# Sheet_Switch_PowerDetect.net
KiCad netlist of a schematic drawn in Altium Designer
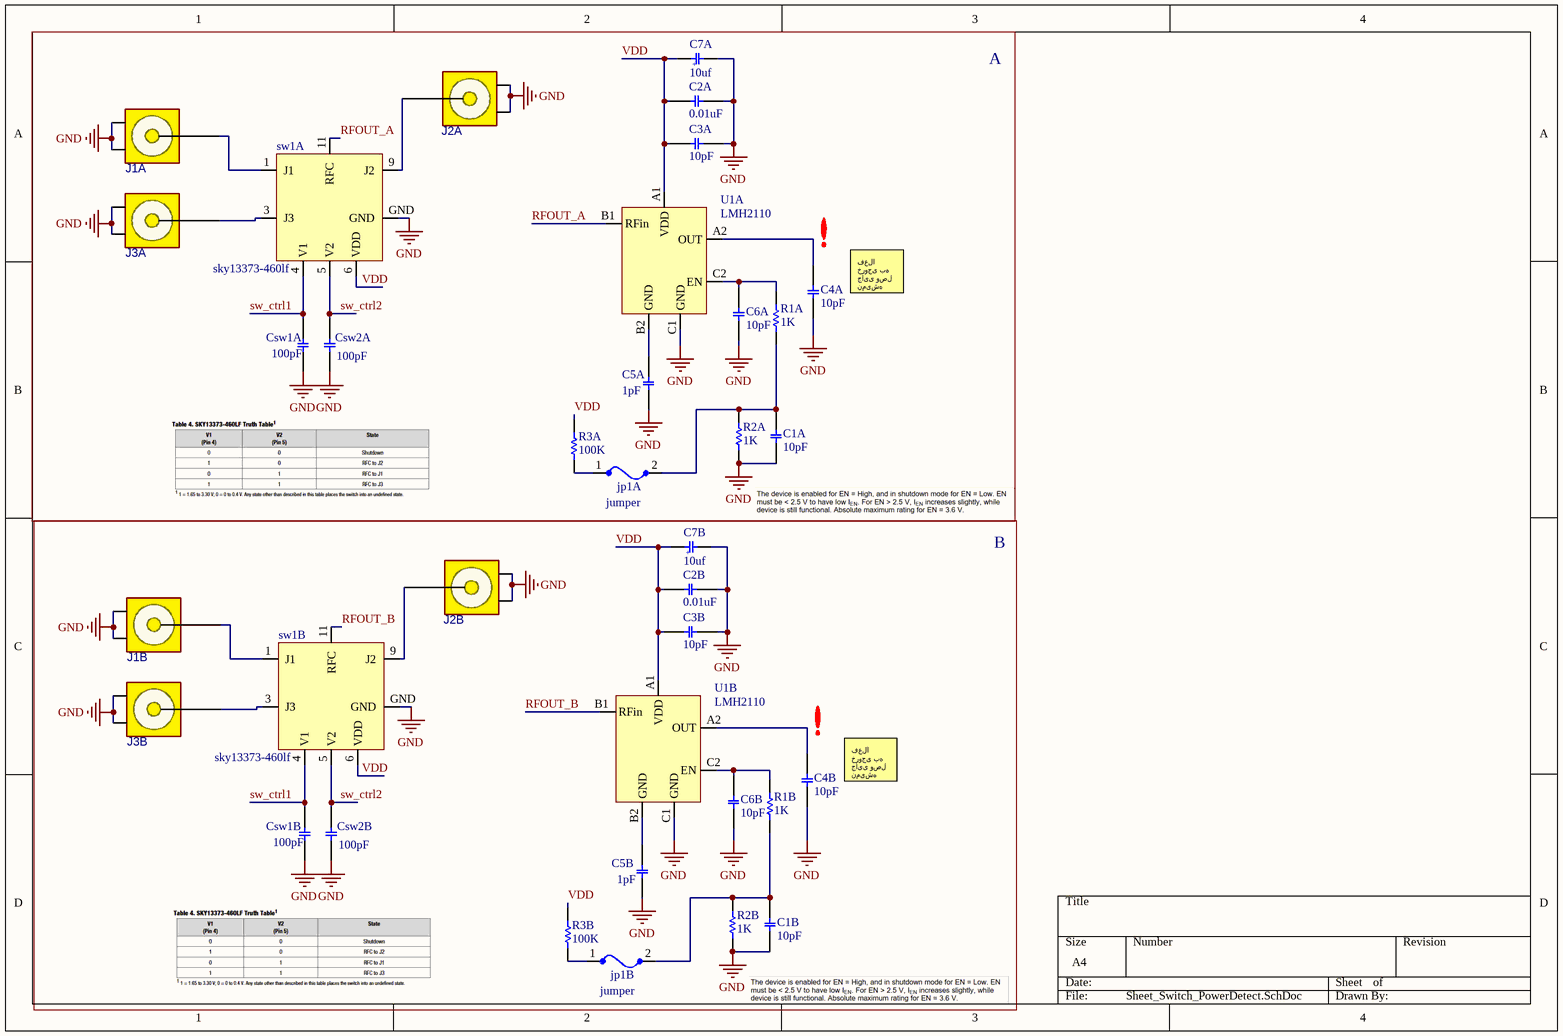
[diagram p0: Sheet_Switch_PowerDetect.SchDoc]

(export (version "E")
  (design (tool "Eeschema 10.0.6"))
  (components
    (comp (ref "C1A")
      (value "10pF")
      (footprint "C0402")
      (description "Capacitor C SMD 0402")
      (fields (field (name "DESIGNED BY:") "MJKhodami"))
      (libsource (lib "project_library") (part "Capacitor C SMD 0402"))
    )
    (comp (ref "C1B")
      (value "10pF")
      (footprint "C0402")
      (description "Capacitor C SMD 0402")
      (fields (field (name "DESIGNED BY:") "MJKhodami"))
      (libsource (lib "project_library") (part "Capacitor C SMD 0402"))
    )
    (comp (ref "C2A")
      (value "0.01uF")
      (footprint "C0402")
      (description "Capacitor C SMD 0402")
      (fields (field (name "DESIGNED BY:") "MJKhodami"))
      (libsource (lib "project_library") (part "Capacitor C SMD 0402"))
    )
    (comp (ref "C2B")
      (value "0.01uF")
      (footprint "C0402")
      (description "Capacitor C SMD 0402")
      (fields (field (name "DESIGNED BY:") "MJKhodami"))
      (libsource (lib "project_library") (part "Capacitor C SMD 0402"))
    )
    (comp (ref "C3A")
      (value "10pF")
      (footprint "C0402")
      (description "Capacitor C SMD 0402")
      (fields (field (name "DESIGNED BY:") "MJKhodami"))
      (libsource (lib "project_library") (part "Capacitor C SMD 0402"))
    )
    (comp (ref "C3B")
      (value "10pF")
      (footprint "C0402")
      (description "Capacitor C SMD 0402")
      (fields (field (name "DESIGNED BY:") "MJKhodami"))
      (libsource (lib "project_library") (part "Capacitor C SMD 0402"))
    )
    (comp (ref "C4A")
      (value "10pF")
      (footprint "C0402")
      (description "Capacitor C SMD 0402")
      (fields (field (name "DESIGNED BY:") "MJKhodami"))
      (libsource (lib "project_library") (part "Capacitor C SMD 0402"))
    )
    (comp (ref "C4B")
      (value "10pF")
      (footprint "C0402")
      (description "Capacitor C SMD 0402")
      (fields (field (name "DESIGNED BY:") "MJKhodami"))
      (libsource (lib "project_library") (part "Capacitor C SMD 0402"))
    )
    (comp (ref "C5A")
      (value "1pF")
      (footprint "C0402")
      (description "Capacitor C SMD 0402")
      (fields (field (name "DESIGNED BY:") "MJKhodami"))
      (libsource (lib "project_library") (part "Capacitor C SMD 0402"))
    )
    (comp (ref "C5B")
      (value "1pF")
      (footprint "C0402")
      (description "Capacitor C SMD 0402")
      (fields (field (name "DESIGNED BY:") "MJKhodami"))
      (libsource (lib "project_library") (part "Capacitor C SMD 0402"))
    )
    (comp (ref "C6A")
      (value "10pF")
      (footprint "C0402")
      (description "Capacitor C SMD 0402")
      (fields (field (name "DESIGNED BY:") "MJKhodami"))
      (libsource (lib "project_library") (part "Capacitor C SMD 0402"))
    )
    (comp (ref "C6B")
      (value "10pF")
      (footprint "C0402")
      (description "Capacitor C SMD 0402")
      (fields (field (name "DESIGNED BY:") "MJKhodami"))
      (libsource (lib "project_library") (part "Capacitor C SMD 0402"))
    )
    (comp (ref "C7A")
      (value "10uf")
      (footprint "CAPP 1206 (3216X18L) Size A")
      (description "Capacitor Tantalum SMD")
      (fields (field (name "DESIGNED BY:") "MJKhodami"))
      (libsource (lib "project_library") (part "Capacitor Tantalum SMD"))
    )
    (comp (ref "C7B")
      (value "10uf")
      (footprint "CAPP 1206 (3216X18L) Size A")
      (description "Capacitor Tantalum SMD")
      (fields (field (name "DESIGNED BY:") "MJKhodami"))
      (libsource (lib "project_library") (part "Capacitor Tantalum SMD"))
    )
    (comp (ref "Csw1A")
      (value "100pF")
      (footprint "C0402")
      (description "Capacitor C SMD 0402")
      (fields (field (name "DESIGNED BY:") "MJKhodami"))
      (libsource (lib "project_library") (part "Capacitor C SMD 0402"))
    )
    (comp (ref "Csw1B")
      (value "100pF")
      (footprint "C0402")
      (description "Capacitor C SMD 0402")
      (fields (field (name "DESIGNED BY:") "MJKhodami"))
      (libsource (lib "project_library") (part "Capacitor C SMD 0402"))
    )
    (comp (ref "Csw2A")
      (value "100pF")
      (footprint "C0402")
      (description "Capacitor C SMD 0402")
      (fields (field (name "DESIGNED BY:") "MJKhodami"))
      (libsource (lib "project_library") (part "Capacitor C SMD 0402"))
    )
    (comp (ref "Csw2B")
      (value "100pF")
      (footprint "C0402")
      (description "Capacitor C SMD 0402")
      (fields (field (name "DESIGNED BY:") "MJKhodami"))
      (libsource (lib "project_library") (part "Capacitor C SMD 0402"))
    )
    (comp (ref "J1A")
      (value "UFL")
      (footprint "UFL")
      (description "CONN, RF, U.FL, STRAIGHT, Ultra Miniature Coaxial")
      (fields (field (name "DESIGNED BY:") "MJKhodami"))
      (libsource (lib "project_library") (part "RF UFL"))
    )
    (comp (ref "J1B")
      (value "UFL")
      (footprint "UFL")
      (description "CONN, RF, U.FL, STRAIGHT, Ultra Miniature Coaxial")
      (fields (field (name "DESIGNED BY:") "MJKhodami"))
      (libsource (lib "project_library") (part "RF UFL"))
    )
    (comp (ref "J2A")
      (value "UFL")
      (footprint "UFL")
      (description "CONN, RF, U.FL, STRAIGHT, Ultra Miniature Coaxial")
      (fields (field (name "DESIGNED BY:") "MJKhodami"))
      (libsource (lib "") (part "RF UFL_1"))
    )
    (comp (ref "J2B")
      (value "UFL")
      (footprint "UFL")
      (description "CONN, RF, U.FL, STRAIGHT, Ultra Miniature Coaxial")
      (fields (field (name "DESIGNED BY:") "MJKhodami"))
      (libsource (lib "") (part "RF UFL_1"))
    )
    (comp (ref "J3A")
      (value "UFL")
      (footprint "UFL")
      (description "CONN, RF, U.FL, STRAIGHT, Ultra Miniature Coaxial")
      (fields (field (name "DESIGNED BY:") "MJKhodami"))
      (libsource (lib "project_library") (part "RF UFL"))
    )
    (comp (ref "J3B")
      (value "UFL")
      (footprint "UFL")
      (description "CONN, RF, U.FL, STRAIGHT, Ultra Miniature Coaxial")
      (fields (field (name "DESIGNED BY:") "MJKhodami"))
      (libsource (lib "project_library") (part "RF UFL"))
    )
    (comp (ref "jp1A")
      (value "jumper")
      (footprint "RES 0402 (1005X04L)")
      (libsource (lib "project_library") (part "jumper"))
    )
    (comp (ref "jp1B")
      (value "jumper")
      (footprint "RES 0402 (1005X04L)")
      (libsource (lib "project_library") (part "jumper"))
    )
    (comp (ref "R1A")
      (value "1K")
      (footprint "SMD-0402-RES")
      (description "Resistor SMD 0402")
      (fields (field (name "DESIGNED BY:") "MJKhodami"))
      (libsource (lib "project_library") (part "Resistor SMD 0402"))
    )
    (comp (ref "R1B")
      (value "1K")
      (footprint "SMD-0402-RES")
      (description "Resistor SMD 0402")
      (fields (field (name "DESIGNED BY:") "MJKhodami"))
      (libsource (lib "project_library") (part "Resistor SMD 0402"))
    )
    (comp (ref "R2A")
      (value "1K")
      (footprint "SMD-0402-RES")
      (description "Resistor SMD 0402")
      (fields (field (name "DESIGNED BY:") "MJKhodami"))
      (libsource (lib "project_library") (part "Resistor SMD 0402"))
    )
    (comp (ref "R2B")
      (value "1K")
      (footprint "SMD-0402-RES")
      (description "Resistor SMD 0402")
      (fields (field (name "DESIGNED BY:") "MJKhodami"))
      (libsource (lib "project_library") (part "Resistor SMD 0402"))
    )
    (comp (ref "R3A")
      (value "100K")
      (footprint "SMD-0402-RES")
      (description "Resistor SMD 0402")
      (fields (field (name "DESIGNED BY:") "MJKhodami"))
      (libsource (lib "project_library") (part "Resistor SMD 0402"))
    )
    (comp (ref "R3B")
      (value "100K")
      (footprint "SMD-0402-RES")
      (description "Resistor SMD 0402")
      (fields (field (name "DESIGNED BY:") "MJKhodami"))
      (libsource (lib "project_library") (part "Resistor SMD 0402"))
    )
    (comp (ref "sw1A")
      (value "sky13373-460lf")
      (footprint "QFN50P200X200X65-13N")
      (libsource (lib "project_library") (part "sky13373-460lf"))
    )
    (comp (ref "sw1B")
      (value "sky13373-460lf")
      (footprint "QFN50P200X200X65-13N")
      (libsource (lib "project_library") (part "sky13373-460lf"))
    )
    (comp (ref "U1A")
      (value "LMH2110")
      (footprint "BGA6N40P3X2_124X84X67N")
      (description "- Wide Supply Range from 2.7 V to 5 V\r\n- Logarithmic Root Mean Square Response")
      (libsource (lib "project_library") (part "LMH2110"))
    )
    (comp (ref "U1B")
      (value "LMH2110")
      (footprint "BGA6N40P3X2_124X84X67N")
      (description "- Wide Supply Range from 2.7 V to 5 V\r\n- Logarithmic Root Mean Square Response")
      (libsource (lib "project_library") (part "LMH2110"))
    )
  )
  (nets
    (net (code "1") (name "/RFOUT_A") (class "Default")
      (node (ref "U1A") (pin "B1") (pinfunction "RFin_B1") (pintype "passive"))
      (node (ref "sw1A") (pin "11") (pinfunction "RFC_11") (pintype "passive"))
    )
    (net (code "2") (name "/RFOUT_B") (class "Default")
      (node (ref "U1B") (pin "B1") (pinfunction "RFin_B1") (pintype "passive"))
      (node (ref "sw1B") (pin "11") (pinfunction "RFC_11") (pintype "passive"))
    )
    (net (code "3") (name "/VDD") (class "Default")
      (node (ref "C2A") (pin "1") (pinfunction "1_1") (pintype "passive"))
      (node (ref "C2B") (pin "1") (pinfunction "1_1") (pintype "passive"))
      (node (ref "C3A") (pin "1") (pinfunction "1_1") (pintype "passive"))
      (node (ref "C3B") (pin "1") (pinfunction "1_1") (pintype "passive"))
      (node (ref "C7A") (pin "2") (pinfunction "2_2") (pintype "passive"))
      (node (ref "C7B") (pin "2") (pinfunction "2_2") (pintype "passive"))
      (node (ref "R3A") (pin "2") (pinfunction "2_2") (pintype "passive"))
      (node (ref "R3B") (pin "2") (pinfunction "2_2") (pintype "passive"))
      (node (ref "U1A") (pin "A1") (pinfunction "VDD_A1") (pintype "passive"))
      (node (ref "U1B") (pin "A1") (pinfunction "VDD_A1") (pintype "passive"))
      (node (ref "sw1A") (pin "6") (pinfunction "VDD_6") (pintype "passive"))
      (node (ref "sw1B") (pin "6") (pinfunction "VDD_6") (pintype "passive"))
    )
    (net (code "4") (name "/sw_ctrl1") (class "Default")
      (node (ref "Csw1A") (pin "2") (pinfunction "2_2") (pintype "passive"))
      (node (ref "Csw1B") (pin "2") (pinfunction "2_2") (pintype "passive"))
      (node (ref "sw1A") (pin "4") (pinfunction "V1_4") (pintype "passive"))
      (node (ref "sw1B") (pin "4") (pinfunction "V1_4") (pintype "passive"))
    )
    (net (code "5") (name "/sw_ctrl2") (class "Default")
      (node (ref "Csw2A") (pin "2") (pinfunction "2_2") (pintype "passive"))
      (node (ref "Csw2B") (pin "2") (pinfunction "2_2") (pintype "passive"))
      (node (ref "sw1A") (pin "5") (pinfunction "V2_5") (pintype "passive"))
      (node (ref "sw1B") (pin "5") (pinfunction "V2_5") (pintype "passive"))
    )
    (net (code "6") (name "GND") (class "Default")
      (node (ref "C1A") (pin "1") (pinfunction "1_1") (pintype "passive"))
      (node (ref "C1B") (pin "1") (pinfunction "1_1") (pintype "passive"))
      (node (ref "C2A") (pin "2") (pinfunction "2_2") (pintype "passive"))
      (node (ref "C2B") (pin "2") (pinfunction "2_2") (pintype "passive"))
      (node (ref "C3A") (pin "2") (pinfunction "2_2") (pintype "passive"))
      (node (ref "C3B") (pin "2") (pinfunction "2_2") (pintype "passive"))
      (node (ref "C4A") (pin "1") (pinfunction "1_1") (pintype "passive"))
      (node (ref "C4B") (pin "1") (pinfunction "1_1") (pintype "passive"))
      (node (ref "C5A") (pin "1") (pinfunction "1_1") (pintype "passive"))
      (node (ref "C5B") (pin "1") (pinfunction "1_1") (pintype "passive"))
      (node (ref "C6A") (pin "1") (pinfunction "1_1") (pintype "passive"))
      (node (ref "C6B") (pin "1") (pinfunction "1_1") (pintype "passive"))
      (node (ref "C7A") (pin "1") (pinfunction "1_1") (pintype "passive"))
      (node (ref "C7B") (pin "1") (pinfunction "1_1") (pintype "passive"))
      (node (ref "Csw1A") (pin "1") (pinfunction "1_1") (pintype "passive"))
      (node (ref "Csw1B") (pin "1") (pinfunction "1_1") (pintype "passive"))
      (node (ref "Csw2A") (pin "1") (pinfunction "1_1") (pintype "passive"))
      (node (ref "Csw2B") (pin "1") (pinfunction "1_1") (pintype "passive"))
      (node (ref "J1A") (pin "2") (pinfunction "G1_2") (pintype "passive"))
      (node (ref "J1A") (pin "3") (pinfunction "G2_3") (pintype "passive"))
      (node (ref "J1B") (pin "2") (pinfunction "G1_2") (pintype "passive"))
      (node (ref "J1B") (pin "3") (pinfunction "G2_3") (pintype "passive"))
      (node (ref "J2A") (pin "2") (pinfunction "G1_2") (pintype "passive"))
      (node (ref "J2A") (pin "3") (pinfunction "G2_3") (pintype "passive"))
      (node (ref "J2B") (pin "2") (pinfunction "G1_2") (pintype "passive"))
      (node (ref "J2B") (pin "3") (pinfunction "G2_3") (pintype "passive"))
      (node (ref "J3A") (pin "2") (pinfunction "G1_2") (pintype "passive"))
      (node (ref "J3A") (pin "3") (pinfunction "G2_3") (pintype "passive"))
      (node (ref "J3B") (pin "2") (pinfunction "G1_2") (pintype "passive"))
      (node (ref "J3B") (pin "3") (pinfunction "G2_3") (pintype "passive"))
      (node (ref "R2A") (pin "1") (pinfunction "1_1") (pintype "passive"))
      (node (ref "R2B") (pin "1") (pinfunction "1_1") (pintype "passive"))
      (node (ref "U1A") (pin "C1") (pinfunction "GND_C1") (pintype "passive"))
      (node (ref "U1B") (pin "C1") (pinfunction "GND_C1") (pintype "passive"))
      (node (ref "sw1A") (pin "GND") (pinfunction "GND_GND") (pintype "passive"))
      (node (ref "sw1B") (pin "GND") (pinfunction "GND_GND") (pintype "passive"))
    )
    (net (code "7") (name "Net-(C1A-Pad2)") (class "Default")
      (node (ref "C1A") (pin "2") (pinfunction "2_2") (pintype "passive"))
      (node (ref "R1A") (pin "1") (pinfunction "1_1") (pintype "passive"))
      (node (ref "R2A") (pin "2") (pinfunction "2_2") (pintype "passive"))
      (node (ref "jp1A") (pin "2") (pinfunction "2_2") (pintype "passive"))
    )
    (net (code "8") (name "Net-(C1B-Pad2)") (class "Default")
      (node (ref "C1B") (pin "2") (pinfunction "2_2") (pintype "passive"))
      (node (ref "R1B") (pin "1") (pinfunction "1_1") (pintype "passive"))
      (node (ref "R2B") (pin "2") (pinfunction "2_2") (pintype "passive"))
      (node (ref "jp1B") (pin "2") (pinfunction "2_2") (pintype "passive"))
    )
    (net (code "9") (name "Net-(C5A-Pad2)") (class "Default")
      (node (ref "C5A") (pin "2") (pinfunction "2_2") (pintype "passive"))
      (node (ref "U1A") (pin "B2") (pinfunction "GND_B2") (pintype "passive"))
    )
    (net (code "10") (name "Net-(C5B-Pad2)") (class "Default")
      (node (ref "C5B") (pin "2") (pinfunction "2_2") (pintype "passive"))
      (node (ref "U1B") (pin "B2") (pinfunction "GND_B2") (pintype "passive"))
    )
    (net (code "11") (name "Net-(J1A-SIG)") (class "Default")
      (node (ref "J1A") (pin "1") (pinfunction "SIG_1") (pintype "passive"))
      (node (ref "sw1A") (pin "1") (pinfunction "J1_1") (pintype "passive"))
    )
    (net (code "12") (name "Net-(J1B-SIG)") (class "Default")
      (node (ref "J1B") (pin "1") (pinfunction "SIG_1") (pintype "passive"))
      (node (ref "sw1B") (pin "1") (pinfunction "J1_1") (pintype "passive"))
    )
    (net (code "13") (name "Net-(J2A-SIG)") (class "Default")
      (node (ref "J2A") (pin "1") (pinfunction "SIG_1") (pintype "passive"))
      (node (ref "sw1A") (pin "9") (pinfunction "J2_9") (pintype "passive"))
    )
    (net (code "14") (name "Net-(J2B-SIG)") (class "Default")
      (node (ref "J2B") (pin "1") (pinfunction "SIG_1") (pintype "passive"))
      (node (ref "sw1B") (pin "9") (pinfunction "J2_9") (pintype "passive"))
    )
    (net (code "15") (name "Net-(J3A-SIG)") (class "Default")
      (node (ref "J3A") (pin "1") (pinfunction "SIG_1") (pintype "passive"))
      (node (ref "sw1A") (pin "3") (pinfunction "J3_3") (pintype "passive"))
    )
    (net (code "16") (name "Net-(J3B-SIG)") (class "Default")
      (node (ref "J3B") (pin "1") (pinfunction "SIG_1") (pintype "passive"))
      (node (ref "sw1B") (pin "3") (pinfunction "J3_3") (pintype "passive"))
    )
    (net (code "17") (name "Net-(R3A-Pad1)") (class "Default")
      (node (ref "R3A") (pin "1") (pinfunction "1_1") (pintype "passive"))
      (node (ref "jp1A") (pin "1") (pinfunction "1_1") (pintype "passive"))
    )
    (net (code "18") (name "Net-(R3B-Pad1)") (class "Default")
      (node (ref "R3B") (pin "1") (pinfunction "1_1") (pintype "passive"))
      (node (ref "jp1B") (pin "1") (pinfunction "1_1") (pintype "passive"))
    )
    (net (code "19") (name "Net-(U1A-EN)") (class "Default")
      (node (ref "C6A") (pin "2") (pinfunction "2_2") (pintype "passive"))
      (node (ref "R1A") (pin "2") (pinfunction "2_2") (pintype "passive"))
      (node (ref "U1A") (pin "C2") (pinfunction "EN_C2") (pintype "passive"))
    )
    (net (code "20") (name "Net-(U1A-OUT)") (class "Default")
      (node (ref "C4A") (pin "2") (pinfunction "2_2") (pintype "passive"))
      (node (ref "U1A") (pin "A2") (pinfunction "OUT_A2") (pintype "passive"))
    )
    (net (code "21") (name "Net-(U1B-EN)") (class "Default")
      (node (ref "C6B") (pin "2") (pinfunction "2_2") (pintype "passive"))
      (node (ref "R1B") (pin "2") (pinfunction "2_2") (pintype "passive"))
      (node (ref "U1B") (pin "C2") (pinfunction "EN_C2") (pintype "passive"))
    )
    (net (code "22") (name "Net-(U1B-OUT)") (class "Default")
      (node (ref "C4B") (pin "2") (pinfunction "2_2") (pintype "passive"))
      (node (ref "U1B") (pin "A2") (pinfunction "OUT_A2") (pintype "passive"))
    )
  )
)
